# uC_board.net
KiCad netlist of a schematic drawn in EAGLE
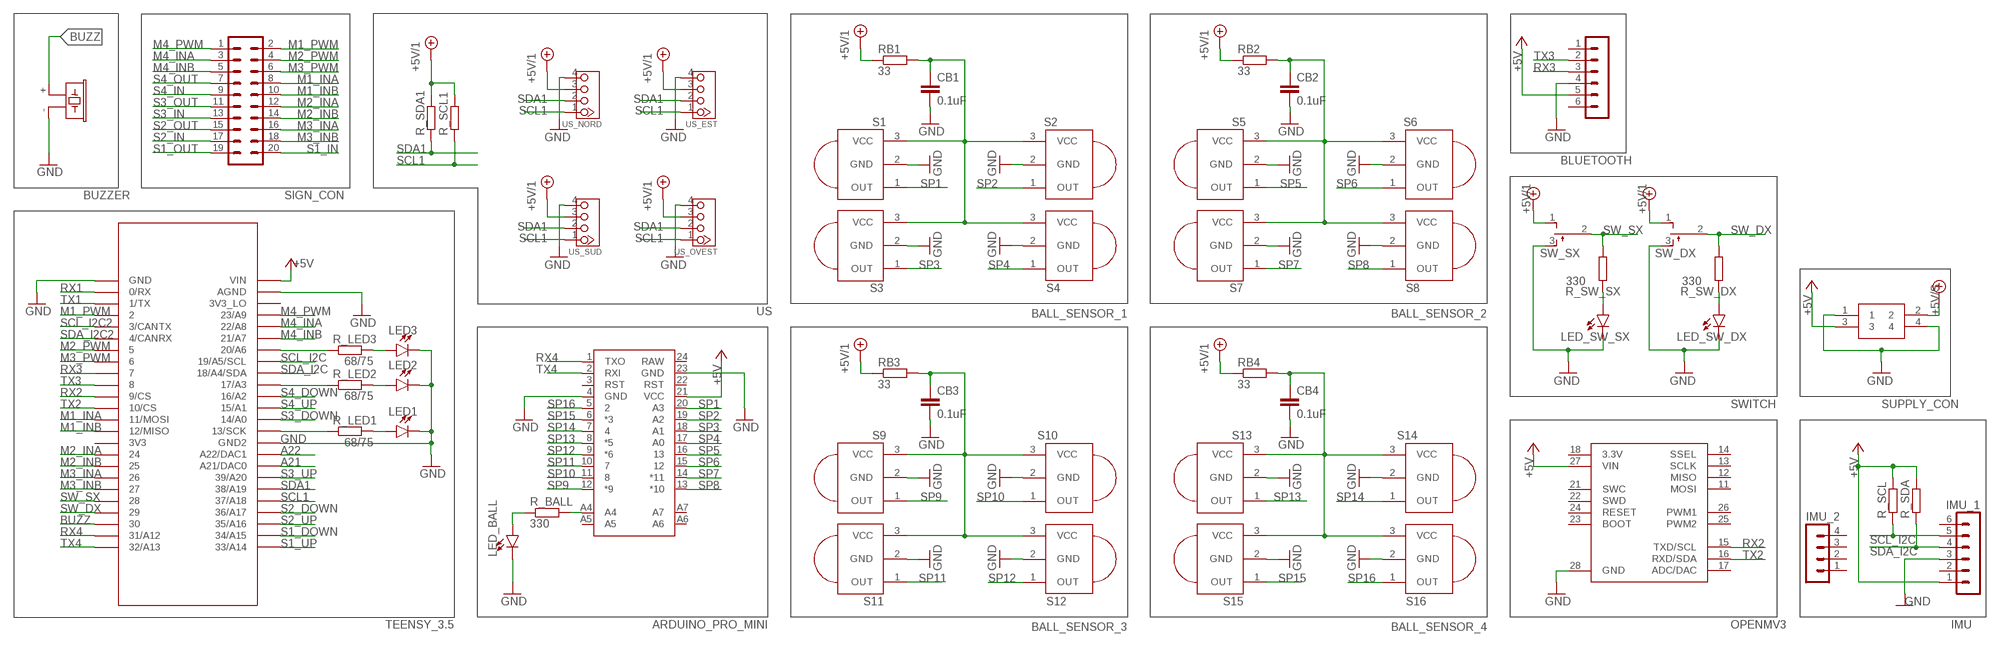
[diagram p0: schematic, sheet 1]

(export (version "E")
  (design (tool "Eeschema 10.0.6"))
  (components
    (comp (ref "ARDUINO_PRO_MINI")
      (value "ARDUINO_PRO_MINI")
      (footprint "eagle-import:ARDUINO_PRO_MINI")
      (libsource (lib "eagle-import") (part "ARDUINO_PRO_MINI"))
    )
    (comp (ref "BLUETOOTH")
      (value "MA06-1")
      (footprint "eagle-import:MA06-1")
      (libsource (lib "eagle-import") (part "MA06-1"))
    )
    (comp (ref "BUZZER")
      (value "F/CM12P")
      (footprint "eagle-import:F_CM12P")
      (libsource (lib "eagle-import") (part "F/CM12P"))
    )
    (comp (ref "CB1")
      (value "0.1uF")
      (footprint "eagle-import:C1206")
      (libsource (lib "eagle-import") (part "C-EUC1206"))
    )
    (comp (ref "CB2")
      (value "0.1uF")
      (footprint "eagle-import:C1206")
      (libsource (lib "eagle-import") (part "C-EUC1206"))
    )
    (comp (ref "CB3")
      (value "0.1uF")
      (footprint "eagle-import:C1206")
      (libsource (lib "eagle-import") (part "C-EUC1206"))
    )
    (comp (ref "CB4")
      (value "0.1uF")
      (footprint "eagle-import:C1206")
      (libsource (lib "eagle-import") (part "C-EUC1206"))
    )
    (comp (ref "IMU_1")
      (value "MA06-1")
      (footprint "eagle-import:MA06-1")
      (libsource (lib "eagle-import") (part "MA06-1"))
    )
    (comp (ref "IMU_2")
      (value "MA04-1")
      (footprint "eagle-import:MA04-1")
      (libsource (lib "eagle-import") (part "MA04-1"))
    )
    (comp (ref "J1")
      (value "39-28-1043")
      (footprint "eagle-import:39-28-1043")
      (fields (field (name "MOUSER_PART_NUMBER") "538-39-28-1043") (field (name "RS_PART_NUMBER") "4841899P"))
      (libsource (lib "eagle-import") (part "39-28-1043"))
    )
    (comp (ref "LED1")
      (value "LED3MM")
      (footprint "eagle-import:LED_3MM")
      (libsource (lib "eagle-import") (part "LED3MM"))
    )
    (comp (ref "LED2")
      (value "LED3MM")
      (footprint "eagle-import:LED_3MM")
      (libsource (lib "eagle-import") (part "LED3MM"))
    )
    (comp (ref "LED3")
      (value "LED3MM")
      (footprint "eagle-import:LED_3MM")
      (libsource (lib "eagle-import") (part "LED3MM"))
    )
    (comp (ref "LED_BALL")
      (value "LED3MM")
      (footprint "eagle-import:LED_3MM")
      (libsource (lib "eagle-import") (part "LED3MM"))
    )
    (comp (ref "LED_SW_DX")
      (value "LED3MM")
      (footprint "eagle-import:LED_3MM")
      (libsource (lib "eagle-import") (part "LED3MM"))
    )
    (comp (ref "LED_SW_SX")
      (value "LED3MM")
      (footprint "eagle-import:LED_3MM")
      (libsource (lib "eagle-import") (part "LED3MM"))
    )
    (comp (ref "RB1")
      (value "33")
      (footprint "eagle-import:R0805")
      (libsource (lib "eagle-import") (part "R-EU_R0805"))
    )
    (comp (ref "RB2")
      (value "33")
      (footprint "eagle-import:R0805")
      (libsource (lib "eagle-import") (part "R-EU_R0805"))
    )
    (comp (ref "RB3")
      (value "33")
      (footprint "eagle-import:R0805")
      (libsource (lib "eagle-import") (part "R-EU_R0805"))
    )
    (comp (ref "RB4")
      (value "33")
      (footprint "eagle-import:R0805")
      (libsource (lib "eagle-import") (part "R-EU_R0805"))
    )
    (comp (ref "R_BALL")
      (value "330")
      (footprint "eagle-import:R1206")
      (libsource (lib "eagle-import") (part "R-EU_R1206"))
    )
    (comp (ref "R_LED1")
      (value "68/75")
      (footprint "eagle-import:R0805")
      (libsource (lib "eagle-import") (part "R-EU_R0805"))
    )
    (comp (ref "R_LED2")
      (value "68/75")
      (footprint "eagle-import:R0805")
      (libsource (lib "eagle-import") (part "R-EU_R0805"))
    )
    (comp (ref "R_LED3")
      (value "68/75")
      (footprint "eagle-import:R0805")
      (libsource (lib "eagle-import") (part "R-EU_R0805"))
    )
    (comp (ref "R_SCL")
      (value "3.3k")
      (footprint "eagle-import:R0805")
      (libsource (lib "eagle-import") (part "R-EU_R0805"))
    )
    (comp (ref "R_SCL1")
      (value "3.3k")
      (footprint "eagle-import:R0805")
      (libsource (lib "eagle-import") (part "R-EU_R0805"))
    )
    (comp (ref "R_SDA")
      (value "3.3k")
      (footprint "eagle-import:R0805")
      (libsource (lib "eagle-import") (part "R-EU_R0805"))
    )
    (comp (ref "R_SDA1")
      (value "3.3k")
      (footprint "eagle-import:R0805")
      (libsource (lib "eagle-import") (part "R-EU_R0805"))
    )
    (comp (ref "R_SW_DX")
      (value "330")
      (footprint "eagle-import:R1206")
      (libsource (lib "eagle-import") (part "R-EU_R1206"))
    )
    (comp (ref "R_SW_SX")
      (value "330")
      (footprint "eagle-import:R1206")
      (libsource (lib "eagle-import") (part "R-EU_R1206"))
    )
    (comp (ref "S1")
      (value "PNA460XM")
      (footprint "eagle-import:PNA460XM")
      (libsource (lib "eagle-import") (part "PNA460XM"))
    )
    (comp (ref "S2")
      (value "PNA460XM")
      (footprint "eagle-import:PNA460XM")
      (libsource (lib "eagle-import") (part "PNA460XM"))
    )
    (comp (ref "S3")
      (value "PNA460XM")
      (footprint "eagle-import:PNA460XM")
      (libsource (lib "eagle-import") (part "PNA460XM"))
    )
    (comp (ref "S4")
      (value "PNA460XM")
      (footprint "eagle-import:PNA460XM")
      (libsource (lib "eagle-import") (part "PNA460XM"))
    )
    (comp (ref "S5")
      (value "PNA460XM")
      (footprint "eagle-import:PNA460XM")
      (libsource (lib "eagle-import") (part "PNA460XM"))
    )
    (comp (ref "S6")
      (value "PNA460XM")
      (footprint "eagle-import:PNA460XM")
      (libsource (lib "eagle-import") (part "PNA460XM"))
    )
    (comp (ref "S7")
      (value "PNA460XM")
      (footprint "eagle-import:PNA460XM")
      (libsource (lib "eagle-import") (part "PNA460XM"))
    )
    (comp (ref "S8")
      (value "PNA460XM")
      (footprint "eagle-import:PNA460XM")
      (libsource (lib "eagle-import") (part "PNA460XM"))
    )
    (comp (ref "S9")
      (value "PNA460XM")
      (footprint "eagle-import:PNA460XM")
      (libsource (lib "eagle-import") (part "PNA460XM"))
    )
    (comp (ref "S10")
      (value "PNA460XM")
      (footprint "eagle-import:PNA460XM")
      (libsource (lib "eagle-import") (part "PNA460XM"))
    )
    (comp (ref "S11")
      (value "PNA460XM")
      (footprint "eagle-import:PNA460XM")
      (libsource (lib "eagle-import") (part "PNA460XM"))
    )
    (comp (ref "S12")
      (value "PNA460XM")
      (footprint "eagle-import:PNA460XM")
      (libsource (lib "eagle-import") (part "PNA460XM"))
    )
    (comp (ref "S13")
      (value "PNA460XM")
      (footprint "eagle-import:PNA460XM")
      (libsource (lib "eagle-import") (part "PNA460XM"))
    )
    (comp (ref "S14")
      (value "PNA460XM")
      (footprint "eagle-import:PNA460XM")
      (libsource (lib "eagle-import") (part "PNA460XM"))
    )
    (comp (ref "S15")
      (value "PNA460XM")
      (footprint "eagle-import:PNA460XM")
      (libsource (lib "eagle-import") (part "PNA460XM"))
    )
    (comp (ref "S16")
      (value "PNA460XM")
      (footprint "eagle-import:PNA460XM")
      (libsource (lib "eagle-import") (part "PNA460XM"))
    )
    (comp (ref "SIGN_CON")
      (value "20V")
      (footprint "eagle-import:20V")
      (libsource (lib "eagle-import") (part "20V"))
    )
    (comp (ref "SW_DX")
      (value "TL38PO")
      (footprint "eagle-import:TL3XPO")
      (libsource (lib "eagle-import") (part "TL38PO"))
    )
    (comp (ref "SW_SX")
      (value "TL38PO")
      (footprint "eagle-import:TL3XPO")
      (libsource (lib "eagle-import") (part "TL38PO"))
    )
    (comp (ref "TEENSY_3.5")
      (value "TEENSY_3.5/3.6")
      (footprint "eagle-import:TEENSY_3.5_3.6")
      (libsource (lib "eagle-import") (part "TEENSY_3.5/3.6"))
    )
    (comp (ref "U$2")
      (value "OPENMV3")
      (footprint "eagle-import:OPENMV3")
      (libsource (lib "eagle-import") (part "OPENMV3"))
    )
    (comp (ref "US_EST")
      (value "TWIG_2.0")
      (footprint "eagle-import:2.0_1X4")
      (libsource (lib "eagle-import") (part "TWIG_2.0"))
    )
    (comp (ref "US_NORD")
      (value "TWIG_2.0")
      (footprint "eagle-import:2.0_1X4")
      (libsource (lib "eagle-import") (part "TWIG_2.0"))
    )
    (comp (ref "US_OVEST")
      (value "TWIG_2.0")
      (footprint "eagle-import:2.0_1X4")
      (libsource (lib "eagle-import") (part "TWIG_2.0"))
    )
    (comp (ref "US_SUD")
      (value "TWIG_2.0")
      (footprint "eagle-import:2.0_1X4")
      (libsource (lib "eagle-import") (part "TWIG_2.0"))
    )
  )
  (nets
    (net (code "1") (name "+5V") (class "Default")
      (node (ref "ARDUINO_PRO_MINI") (pin "21") (pinfunction "VCC_21") (pintype "power_in"))
      (node (ref "BLUETOOTH") (pin "5") (pinfunction "5_5") (pintype "passive"))
      (node (ref "IMU_1") (pin "1") (pinfunction "1_1") (pintype "passive"))
      (node (ref "J1") (pin "3") (pinfunction "3_3") (pintype "bidirectional"))
      (node (ref "R_SCL") (pin "2") (pinfunction "2_2") (pintype "passive"))
      (node (ref "R_SDA") (pin "2") (pinfunction "2_2") (pintype "passive"))
      (node (ref "TEENSY_3.5") (pin "VIN") (pinfunction "VIN_VIN") (pintype "bidirectional"))
      (node (ref "U$2") (pin "27") (pinfunction "VIN_27") (pintype "power_in"))
    )
    (net (code "2") (name "+5V{slash}1") (class "Default")
      (node (ref "J1") (pin "2") (pinfunction "2_2") (pintype "bidirectional"))
      (node (ref "RB1") (pin "1") (pinfunction "1_1") (pintype "passive"))
      (node (ref "RB2") (pin "1") (pinfunction "1_1") (pintype "passive"))
      (node (ref "RB3") (pin "1") (pinfunction "1_1") (pintype "passive"))
      (node (ref "RB4") (pin "1") (pinfunction "1_1") (pintype "passive"))
      (node (ref "R_SCL1") (pin "2") (pinfunction "2_2") (pintype "passive"))
      (node (ref "R_SDA1") (pin "2") (pinfunction "2_2") (pintype "passive"))
      (node (ref "SW_DX") (pin "1") (pinfunction "O_1") (pintype "passive"))
      (node (ref "SW_SX") (pin "1") (pinfunction "O_1") (pintype "passive"))
      (node (ref "US_EST") (pin "3") (pinfunction "3_3") (pintype "bidirectional"))
      (node (ref "US_NORD") (pin "3") (pinfunction "3_3") (pintype "bidirectional"))
      (node (ref "US_OVEST") (pin "3") (pinfunction "3_3") (pintype "bidirectional"))
      (node (ref "US_SUD") (pin "3") (pinfunction "3_3") (pintype "bidirectional"))
    )
    (net (code "3") (name "/3.3V") (class "Default")
      (node (ref "U$2") (pin "18") (pinfunction "3.3V_18") (pintype "power_in"))
    )
    (net (code "4") (name "/A21") (class "Default")
      (node (ref "TEENSY_3.5") (pin "21/DAC0") (pinfunction "A21/DAC0_21/DAC0") (pintype "bidirectional"))
    )
    (net (code "5") (name "/A22") (class "Default")
      (node (ref "TEENSY_3.5") (pin "A22/DAC1") (pinfunction "A22/DAC1_A22/DAC1") (pintype "bidirectional"))
    )
    (net (code "6") (name "/M1_INA") (class "Default")
      (node (ref "SIGN_CON") (pin "8") (pinfunction "8_8") (pintype "passive"))
      (node (ref "TEENSY_3.5") (pin "11/MOSI") (pinfunction "11/MOSI_11/MOSI") (pintype "bidirectional"))
    )
    (net (code "7") (name "/M1_INB") (class "Default")
      (node (ref "SIGN_CON") (pin "10") (pinfunction "10_10") (pintype "passive"))
      (node (ref "TEENSY_3.5") (pin "12/MISO") (pinfunction "12/MISO_12/MISO") (pintype "bidirectional"))
    )
    (net (code "8") (name "/M1_PWM") (class "Default")
      (node (ref "SIGN_CON") (pin "2") (pinfunction "2_2") (pintype "passive"))
      (node (ref "TEENSY_3.5") (pin "2") (pinfunction "2_2") (pintype "bidirectional"))
    )
    (net (code "9") (name "/M2_INA") (class "Default")
      (node (ref "SIGN_CON") (pin "12") (pinfunction "12_12") (pintype "passive"))
      (node (ref "TEENSY_3.5") (pin "24") (pinfunction "24_24") (pintype "bidirectional"))
    )
    (net (code "10") (name "/M2_INB") (class "Default")
      (node (ref "SIGN_CON") (pin "14") (pinfunction "14_14") (pintype "passive"))
      (node (ref "TEENSY_3.5") (pin "25") (pinfunction "25_25") (pintype "bidirectional"))
    )
    (net (code "11") (name "/M2_PWM") (class "Default")
      (node (ref "SIGN_CON") (pin "4") (pinfunction "4_4") (pintype "passive"))
      (node (ref "TEENSY_3.5") (pin "5") (pinfunction "5_5") (pintype "bidirectional"))
    )
    (net (code "12") (name "/M3_INA") (class "Default")
      (node (ref "SIGN_CON") (pin "16") (pinfunction "16_16") (pintype "passive"))
      (node (ref "TEENSY_3.5") (pin "26") (pinfunction "26_26") (pintype "bidirectional"))
    )
    (net (code "13") (name "/M3_INB") (class "Default")
      (node (ref "SIGN_CON") (pin "18") (pinfunction "18_18") (pintype "passive"))
      (node (ref "TEENSY_3.5") (pin "27") (pinfunction "27_27") (pintype "bidirectional"))
    )
    (net (code "14") (name "/M3_PWM") (class "Default")
      (node (ref "SIGN_CON") (pin "6") (pinfunction "6_6") (pintype "passive"))
      (node (ref "TEENSY_3.5") (pin "6") (pinfunction "6_6") (pintype "bidirectional"))
    )
    (net (code "15") (name "/M4_INA") (class "Default")
      (node (ref "SIGN_CON") (pin "3") (pinfunction "3_3") (pintype "passive"))
      (node (ref "TEENSY_3.5") (pin "22/A8") (pinfunction "22/A8_22/A8") (pintype "bidirectional"))
    )
    (net (code "16") (name "/M4_INB") (class "Default")
      (node (ref "SIGN_CON") (pin "5") (pinfunction "5_5") (pintype "passive"))
      (node (ref "TEENSY_3.5") (pin "21/A7") (pinfunction "21/A7_21/A7") (pintype "bidirectional"))
    )
    (net (code "17") (name "/M4_PWM") (class "Default")
      (node (ref "SIGN_CON") (pin "1") (pinfunction "1_1") (pintype "passive"))
      (node (ref "TEENSY_3.5") (pin "23/A9") (pinfunction "23/A9_23/A9") (pintype "bidirectional"))
    )
    (net (code "18") (name "/RAW") (class "Default")
      (node (ref "ARDUINO_PRO_MINI") (pin "24") (pinfunction "RAW_24") (pintype "power_in"))
    )
    (net (code "19") (name "/RX1") (class "Default")
      (node (ref "TEENSY_3.5") (pin "0/RX") (pinfunction "0/RX_0/RX") (pintype "bidirectional"))
    )
    (net (code "20") (name "/RX2") (class "Default")
      (node (ref "TEENSY_3.5") (pin "9/CS") (pinfunction "9/CS_9/CS") (pintype "bidirectional"))
      (node (ref "U$2") (pin "15") (pinfunction "TXD/SCL_15") (pintype "bidirectional"))
    )
    (net (code "21") (name "/RX3") (class "Default")
      (node (ref "BLUETOOTH") (pin "3") (pinfunction "3_3") (pintype "passive"))
      (node (ref "TEENSY_3.5") (pin "7") (pinfunction "7_7") (pintype "bidirectional"))
    )
    (net (code "22") (name "/RX4") (class "Default")
      (node (ref "ARDUINO_PRO_MINI") (pin "1") (pinfunction "TXO_1") (pintype "bidirectional"))
      (node (ref "TEENSY_3.5") (pin "31/A12") (pinfunction "31/A12_31/A12") (pintype "bidirectional"))
    )
    (net (code "23") (name "/S1_DOWN") (class "Default")
      (node (ref "TEENSY_3.5") (pin "34/A15") (pinfunction "34/A15_34/A15") (pintype "bidirectional"))
    )
    (net (code "24") (name "/S1_IN") (class "Default")
      (node (ref "SIGN_CON") (pin "20") (pinfunction "20_20") (pintype "passive"))
    )
    (net (code "25") (name "/S1_OUT") (class "Default")
      (node (ref "SIGN_CON") (pin "19") (pinfunction "19_19") (pintype "passive"))
    )
    (net (code "26") (name "/S1_UP") (class "Default")
      (node (ref "TEENSY_3.5") (pin "33/A14") (pinfunction "33/A14_33/A14") (pintype "bidirectional"))
    )
    (net (code "27") (name "/S2_DOWN") (class "Default")
      (node (ref "TEENSY_3.5") (pin "36/A17") (pinfunction "36/A17_36/A17") (pintype "bidirectional"))
    )
    (net (code "28") (name "/S2_IN") (class "Default")
      (node (ref "SIGN_CON") (pin "17") (pinfunction "17_17") (pintype "passive"))
    )
    (net (code "29") (name "/S2_OUT") (class "Default")
      (node (ref "SIGN_CON") (pin "15") (pinfunction "15_15") (pintype "passive"))
    )
    (net (code "30") (name "/S2_UP") (class "Default")
      (node (ref "TEENSY_3.5") (pin "35/A16") (pinfunction "35/A16_35/A16") (pintype "bidirectional"))
    )
    (net (code "31") (name "/S3_DOWN") (class "Default")
      (node (ref "TEENSY_3.5") (pin "14/A0") (pinfunction "14/A0_14/A0") (pintype "bidirectional"))
    )
    (net (code "32") (name "/S3_IN") (class "Default")
      (node (ref "SIGN_CON") (pin "13") (pinfunction "13_13") (pintype "passive"))
    )
    (net (code "33") (name "/S3_OUT") (class "Default")
      (node (ref "SIGN_CON") (pin "11") (pinfunction "11_11") (pintype "passive"))
    )
    (net (code "34") (name "/S3_UP") (class "Default")
      (node (ref "TEENSY_3.5") (pin "39/A20") (pinfunction "39/A20_39/A20") (pintype "bidirectional"))
    )
    (net (code "35") (name "/S4_DOWN") (class "Default")
      (node (ref "TEENSY_3.5") (pin "16/A2") (pinfunction "16/A2_16/A2") (pintype "bidirectional"))
    )
    (net (code "36") (name "/S4_IN") (class "Default")
      (node (ref "SIGN_CON") (pin "9") (pinfunction "9_9") (pintype "passive"))
    )
    (net (code "37") (name "/S4_OUT") (class "Default")
      (node (ref "SIGN_CON") (pin "7") (pinfunction "7_7") (pintype "passive"))
    )
    (net (code "38") (name "/S4_UP") (class "Default")
      (node (ref "TEENSY_3.5") (pin "15/A1") (pinfunction "15/A1_15/A1") (pintype "bidirectional"))
    )
    (net (code "39") (name "/SCL1") (class "Default")
      (node (ref "R_SCL1") (pin "1") (pinfunction "1_1") (pintype "passive"))
      (node (ref "TEENSY_3.5") (pin "37/A18") (pinfunction "37/A18_37/A18") (pintype "bidirectional"))
      (node (ref "US_EST") (pin "1") (pinfunction "1_1") (pintype "bidirectional"))
      (node (ref "US_NORD") (pin "1") (pinfunction "1_1") (pintype "bidirectional"))
      (node (ref "US_OVEST") (pin "1") (pinfunction "1_1") (pintype "bidirectional"))
      (node (ref "US_SUD") (pin "1") (pinfunction "1_1") (pintype "bidirectional"))
    )
    (net (code "40") (name "/SCL_I2C") (class "Default")
      (node (ref "IMU_1") (pin "5") (pinfunction "5_5") (pintype "passive"))
      (node (ref "R_SCL") (pin "1") (pinfunction "1_1") (pintype "passive"))
      (node (ref "TEENSY_3.5") (pin "19/A5/SCL") (pinfunction "19/A5/SCL_19/A5/SCL") (pintype "bidirectional"))
    )
    (net (code "41") (name "/SCL_I2C2") (class "Default")
      (node (ref "TEENSY_3.5") (pin "3/CANTX") (pinfunction "3/CANTX_3/CANTX") (pintype "bidirectional"))
    )
    (net (code "42") (name "/SDA1") (class "Default")
      (node (ref "R_SDA1") (pin "1") (pinfunction "1_1") (pintype "passive"))
      (node (ref "TEENSY_3.5") (pin "38/A19") (pinfunction "38/A19_38/A19") (pintype "bidirectional"))
      (node (ref "US_EST") (pin "2") (pinfunction "2_2") (pintype "bidirectional"))
      (node (ref "US_NORD") (pin "2") (pinfunction "2_2") (pintype "bidirectional"))
      (node (ref "US_OVEST") (pin "2") (pinfunction "2_2") (pintype "bidirectional"))
      (node (ref "US_SUD") (pin "2") (pinfunction "2_2") (pintype "bidirectional"))
    )
    (net (code "43") (name "/SDA_I2C") (class "Default")
      (node (ref "IMU_1") (pin "4") (pinfunction "4_4") (pintype "passive"))
      (node (ref "R_SDA") (pin "1") (pinfunction "1_1") (pintype "passive"))
      (node (ref "TEENSY_3.5") (pin "18/A4/SDA") (pinfunction "18/A4/SDA_18/A4/SDA") (pintype "bidirectional"))
    )
    (net (code "44") (name "/SDA_I2C2") (class "Default")
      (node (ref "TEENSY_3.5") (pin "4/CANRX") (pinfunction "4/CANRX_4/CANRX") (pintype "bidirectional"))
    )
    (net (code "45") (name "/SP1") (class "Default")
      (node (ref "ARDUINO_PRO_MINI") (pin "20") (pinfunction "A3_20") (pintype "bidirectional"))
      (node (ref "S1") (pin "1") (pinfunction "OUT_1") (pintype "output"))
    )
    (net (code "46") (name "/SP2") (class "Default")
      (node (ref "ARDUINO_PRO_MINI") (pin "19") (pinfunction "A2_19") (pintype "bidirectional"))
      (node (ref "S2") (pin "1") (pinfunction "OUT_1") (pintype "output"))
    )
    (net (code "47") (name "/SP3") (class "Default")
      (node (ref "ARDUINO_PRO_MINI") (pin "18") (pinfunction "A1_18") (pintype "bidirectional"))
      (node (ref "S3") (pin "1") (pinfunction "OUT_1") (pintype "output"))
    )
    (net (code "48") (name "/SP4") (class "Default")
      (node (ref "ARDUINO_PRO_MINI") (pin "17") (pinfunction "A0_17") (pintype "bidirectional"))
      (node (ref "S4") (pin "1") (pinfunction "OUT_1") (pintype "output"))
    )
    (net (code "49") (name "/SP5") (class "Default")
      (node (ref "ARDUINO_PRO_MINI") (pin "16") (pinfunction "13_16") (pintype "bidirectional"))
      (node (ref "S5") (pin "1") (pinfunction "OUT_1") (pintype "output"))
    )
    (net (code "50") (name "/SP6") (class "Default")
      (node (ref "ARDUINO_PRO_MINI") (pin "15") (pinfunction "12_15") (pintype "bidirectional"))
      (node (ref "S6") (pin "1") (pinfunction "OUT_1") (pintype "output"))
    )
    (net (code "51") (name "/SP7") (class "Default")
      (node (ref "ARDUINO_PRO_MINI") (pin "14") (pinfunction "*11_14") (pintype "bidirectional"))
      (node (ref "S7") (pin "1") (pinfunction "OUT_1") (pintype "output"))
    )
    (net (code "52") (name "/SP8") (class "Default")
      (node (ref "ARDUINO_PRO_MINI") (pin "13") (pinfunction "*10_13") (pintype "bidirectional"))
      (node (ref "S8") (pin "1") (pinfunction "OUT_1") (pintype "output"))
    )
    (net (code "53") (name "/SP9") (class "Default")
      (node (ref "ARDUINO_PRO_MINI") (pin "12") (pinfunction "*9_12") (pintype "bidirectional"))
      (node (ref "S9") (pin "1") (pinfunction "OUT_1") (pintype "output"))
    )
    (net (code "54") (name "/SP10") (class "Default")
      (node (ref "ARDUINO_PRO_MINI") (pin "11") (pinfunction "8_11") (pintype "bidirectional"))
      (node (ref "S10") (pin "1") (pinfunction "OUT_1") (pintype "output"))
    )
    (net (code "55") (name "/SP11") (class "Default")
      (node (ref "ARDUINO_PRO_MINI") (pin "10") (pinfunction "7_10") (pintype "bidirectional"))
      (node (ref "S11") (pin "1") (pinfunction "OUT_1") (pintype "output"))
    )
    (net (code "56") (name "/SP12") (class "Default")
      (node (ref "ARDUINO_PRO_MINI") (pin "9") (pinfunction "*6_9") (pintype "bidirectional"))
      (node (ref "S12") (pin "1") (pinfunction "OUT_1") (pintype "output"))
    )
    (net (code "57") (name "/SP13") (class "Default")
      (node (ref "ARDUINO_PRO_MINI") (pin "8") (pinfunction "*5_8") (pintype "bidirectional"))
      (node (ref "S13") (pin "1") (pinfunction "OUT_1") (pintype "output"))
    )
    (net (code "58") (name "/SP14") (class "Default")
      (node (ref "ARDUINO_PRO_MINI") (pin "7") (pinfunction "4_7") (pintype "bidirectional"))
      (node (ref "S14") (pin "1") (pinfunction "OUT_1") (pintype "output"))
    )
    (net (code "59") (name "/SP15") (class "Default")
      (node (ref "ARDUINO_PRO_MINI") (pin "6") (pinfunction "*3_6") (pintype "bidirectional"))
      (node (ref "S15") (pin "1") (pinfunction "OUT_1") (pintype "output"))
    )
    (net (code "60") (name "/SP16") (class "Default")
      (node (ref "ARDUINO_PRO_MINI") (pin "5") (pinfunction "2_5") (pintype "bidirectional"))
      (node (ref "S16") (pin "1") (pinfunction "OUT_1") (pintype "output"))
    )
    (net (code "61") (name "/SW_DX") (class "Default")
      (node (ref "R_SW_DX") (pin "2") (pinfunction "2_2") (pintype "passive"))
      (node (ref "SW_DX") (pin "2") (pinfunction "P_2") (pintype "passive"))
      (node (ref "TEENSY_3.5") (pin "29") (pinfunction "29_29") (pintype "bidirectional"))
    )
    (net (code "62") (name "/SW_SX") (class "Default")
      (node (ref "R_SW_SX") (pin "2") (pinfunction "2_2") (pintype "passive"))
      (node (ref "SW_SX") (pin "2") (pinfunction "P_2") (pintype "passive"))
      (node (ref "TEENSY_3.5") (pin "28") (pinfunction "28_28") (pintype "bidirectional"))
    )
    (net (code "63") (name "/TX1") (class "Default")
      (node (ref "TEENSY_3.5") (pin "1/TX") (pinfunction "1/TX_1/TX") (pintype "bidirectional"))
    )
    (net (code "64") (name "/TX2") (class "Default")
      (node (ref "TEENSY_3.5") (pin "10/CS") (pinfunction "10/CS_10/CS") (pintype "bidirectional"))
      (node (ref "U$2") (pin "16") (pinfunction "RXD/SDA_16") (pintype "bidirectional"))
    )
    (net (code "65") (name "/TX3") (class "Default")
      (node (ref "BLUETOOTH") (pin "2") (pinfunction "2_2") (pintype "passive"))
      (node (ref "TEENSY_3.5") (pin "8") (pinfunction "8_8") (pintype "bidirectional"))
    )
    (net (code "66") (name "/TX4") (class "Default")
      (node (ref "ARDUINO_PRO_MINI") (pin "2") (pinfunction "RXI_2") (pintype "bidirectional"))
      (node (ref "TEENSY_3.5") (pin "32/A13") (pinfunction "32/A13_32/A13") (pintype "bidirectional"))
    )
    (net (code "67") (name "BUZZ") (class "Default")
      (node (ref "BUZZER") (pin "+") (pinfunction "1_+") (pintype "passive"))
      (node (ref "TEENSY_3.5") (pin "30") (pinfunction "30_30") (pintype "bidirectional"))
    )
    (net (code "68") (name "GND") (class "Default")
      (node (ref "ARDUINO_PRO_MINI") (pin "23") (pinfunction "GND_23") (pintype "power_in"))
      (node (ref "ARDUINO_PRO_MINI") (pin "4") (pinfunction "GND_4") (pintype "power_in"))
      (node (ref "BLUETOOTH") (pin "4") (pinfunction "4_4") (pintype "passive"))
      (node (ref "BUZZER") (pin "-") (pinfunction "2_-") (pintype "passive"))
      (node (ref "CB1") (pin "2") (pinfunction "2_2") (pintype "passive"))
      (node (ref "CB2") (pin "2") (pinfunction "2_2") (pintype "passive"))
      (node (ref "CB3") (pin "2") (pinfunction "2_2") (pintype "passive"))
      (node (ref "CB4") (pin "2") (pinfunction "2_2") (pintype "passive"))
      (node (ref "IMU_1") (pin "3") (pinfunction "3_3") (pintype "passive"))
      (node (ref "J1") (pin "1") (pinfunction "1_1") (pintype "bidirectional"))
      (node (ref "J1") (pin "4") (pinfunction "4_4") (pintype "bidirectional"))
      (node (ref "LED1") (pin "K") (pinfunction "C_K") (pintype "passive"))
      (node (ref "LED2") (pin "K") (pinfunction "C_K") (pintype "passive"))
      (node (ref "LED3") (pin "K") (pinfunction "C_K") (pintype "passive"))
      (node (ref "LED_BALL") (pin "K") (pinfunction "C_K") (pintype "passive"))
      (node (ref "LED_SW_DX") (pin "K") (pinfunction "C_K") (pintype "passive"))
      (node (ref "LED_SW_SX") (pin "K") (pinfunction "C_K") (pintype "passive"))
      (node (ref "S1") (pin "2") (pinfunction "GND_2") (pintype "power_in"))
      (node (ref "S10") (pin "2") (pinfunction "GND_2") (pintype "power_in"))
      (node (ref "S11") (pin "2") (pinfunction "GND_2") (pintype "power_in"))
      (node (ref "S12") (pin "2") (pinfunction "GND_2") (pintype "power_in"))
      (node (ref "S13") (pin "2") (pinfunction "GND_2") (pintype "power_in"))
      (node (ref "S14") (pin "2") (pinfunction "GND_2") (pintype "power_in"))
      (node (ref "S15") (pin "2") (pinfunction "GND_2") (pintype "power_in"))
      (node (ref "S16") (pin "2") (pinfunction "GND_2") (pintype "power_in"))
      (node (ref "S2") (pin "2") (pinfunction "GND_2") (pintype "power_in"))
      (node (ref "S3") (pin "2") (pinfunction "GND_2") (pintype "power_in"))
      (node (ref "S4") (pin "2") (pinfunction "GND_2") (pintype "power_in"))
      (node (ref "S5") (pin "2") (pinfunction "GND_2") (pintype "power_in"))
      (node (ref "S6") (pin "2") (pinfunction "GND_2") (pintype "power_in"))
      (node (ref "S7") (pin "2") (pinfunction "GND_2") (pintype "power_in"))
      (node (ref "S8") (pin "2") (pinfunction "GND_2") (pintype "power_in"))
      (node (ref "S9") (pin "2") (pinfunction "GND_2") (pintype "power_in"))
      (node (ref "SW_DX") (pin "3") (pinfunction "S_3") (pintype "passive"))
      (node (ref "SW_SX") (pin "3") (pinfunction "S_3") (pintype "passive"))
      (node (ref "TEENSY_3.5") (pin "AGND") (pinfunction "AGND_AGND") (pintype "bidirectional"))
      (node (ref "TEENSY_3.5") (pin "GND") (pinfunction "GND_GND") (pintype "bidirectional"))
      (node (ref "TEENSY_3.5") (pin "GND2") (pinfunction "GND2_GND2") (pintype "bidirectional"))
      (node (ref "U$2") (pin "28") (pinfunction "GND_28") (pintype "power_in"))
      (node (ref "US_EST") (pin "4") (pinfunction "4_4") (pintype "bidirectional"))
      (node (ref "US_NORD") (pin "4") (pinfunction "4_4") (pintype "bidirectional"))
      (node (ref "US_OVEST") (pin "4") (pinfunction "4_4") (pintype "bidirectional"))
      (node (ref "US_SUD") (pin "4") (pinfunction "4_4") (pintype "bidirectional"))
    )
    (net (code "69") (name "Net-(ARDUINO_PRO_MINI-PadA4)") (class "Default")
      (node (ref "ARDUINO_PRO_MINI") (pin "A4") (pinfunction "A4_A4") (pintype "bidirectional"))
      (node (ref "R_BALL") (pin "2") (pinfunction "2_2") (pintype "passive"))
    )
    (net (code "70") (name "Net-(LED1-PadA)") (class "Default")
      (node (ref "LED1") (pin "A") (pinfunction "A_A") (pintype "passive"))
      (node (ref "R_LED1") (pin "2") (pinfunction "2_2") (pintype "passive"))
    )
    (net (code "71") (name "Net-(LED2-PadA)") (class "Default")
      (node (ref "LED2") (pin "A") (pinfunction "A_A") (pintype "passive"))
      (node (ref "R_LED2") (pin "2") (pinfunction "2_2") (pintype "passive"))
    )
    (net (code "72") (name "Net-(LED3-PadA)") (class "Default")
      (node (ref "LED3") (pin "A") (pinfunction "A_A") (pintype "passive"))
      (node (ref "R_LED3") (pin "2") (pinfunction "2_2") (pintype "passive"))
    )
    (net (code "73") (name "Net-(LED_BALL-PadA)") (class "Default")
      (node (ref "LED_BALL") (pin "A") (pinfunction "A_A") (pintype "passive"))
      (node (ref "R_BALL") (pin "1") (pinfunction "1_1") (pintype "passive"))
    )
    (net (code "74") (name "Net-(LED_SW_DX-PadA)") (class "Default")
      (node (ref "LED_SW_DX") (pin "A") (pinfunction "A_A") (pintype "passive"))
      (node (ref "R_SW_DX") (pin "1") (pinfunction "1_1") (pintype "passive"))
    )
    (net (code "75") (name "Net-(LED_SW_SX-PadA)") (class "Default")
      (node (ref "LED_SW_SX") (pin "A") (pinfunction "A_A") (pintype "passive"))
      (node (ref "R_SW_SX") (pin "1") (pinfunction "1_1") (pintype "passive"))
    )
    (net (code "76") (name "Net-(R_LED1-Pad1)") (class "Default")
      (node (ref "R_LED1") (pin "1") (pinfunction "1_1") (pintype "passive"))
      (node (ref "TEENSY_3.5") (pin "13/SCK") (pinfunction "13/SCK_13/SCK") (pintype "bidirectional"))
    )
    (net (code "77") (name "Net-(R_LED2-Pad1)") (class "Default")
      (node (ref "R_LED2") (pin "1") (pinfunction "1_1") (pintype "passive"))
      (node (ref "TEENSY_3.5") (pin "17/A3") (pinfunction "17/A3_17/A3") (pintype "bidirectional"))
    )
    (net (code "78") (name "Net-(R_LED3-Pad1)") (class "Default")
      (node (ref "R_LED3") (pin "1") (pinfunction "1_1") (pintype "passive"))
      (node (ref "TEENSY_3.5") (pin "20/A6") (pinfunction "20/A6_20/A6") (pintype "bidirectional"))
    )
    (net (code "79") (name "Net-(S1-VCC)") (class "Default")
      (node (ref "CB1") (pin "1") (pinfunction "1_1") (pintype "passive"))
      (node (ref "RB1") (pin "2") (pinfunction "2_2") (pintype "passive"))
      (node (ref "S1") (pin "3") (pinfunction "VCC_3") (pintype "power_in"))
      (node (ref "S2") (pin "3") (pinfunction "VCC_3") (pintype "power_in"))
      (node (ref "S3") (pin "3") (pinfunction "VCC_3") (pintype "power_in"))
      (node (ref "S4") (pin "3") (pinfunction "VCC_3") (pintype "power_in"))
    )
    (net (code "80") (name "Net-(S5-VCC)") (class "Default")
      (node (ref "CB2") (pin "1") (pinfunction "1_1") (pintype "passive"))
      (node (ref "RB2") (pin "2") (pinfunction "2_2") (pintype "passive"))
      (node (ref "S5") (pin "3") (pinfunction "VCC_3") (pintype "power_in"))
      (node (ref "S6") (pin "3") (pinfunction "VCC_3") (pintype "power_in"))
      (node (ref "S7") (pin "3") (pinfunction "VCC_3") (pintype "power_in"))
      (node (ref "S8") (pin "3") (pinfunction "VCC_3") (pintype "power_in"))
    )
    (net (code "81") (name "Net-(S10-VCC)") (class "Default")
      (node (ref "CB3") (pin "1") (pinfunction "1_1") (pintype "passive"))
      (node (ref "RB3") (pin "2") (pinfunction "2_2") (pintype "passive"))
      (node (ref "S10") (pin "3") (pinfunction "VCC_3") (pintype "power_in"))
      (node (ref "S11") (pin "3") (pinfunction "VCC_3") (pintype "power_in"))
      (node (ref "S12") (pin "3") (pinfunction "VCC_3") (pintype "power_in"))
      (node (ref "S9") (pin "3") (pinfunction "VCC_3") (pintype "power_in"))
    )
    (net (code "82") (name "Net-(S13-VCC)") (class "Default")
      (node (ref "CB4") (pin "1") (pinfunction "1_1") (pintype "passive"))
      (node (ref "RB4") (pin "2") (pinfunction "2_2") (pintype "passive"))
      (node (ref "S13") (pin "3") (pinfunction "VCC_3") (pintype "power_in"))
      (node (ref "S14") (pin "3") (pinfunction "VCC_3") (pintype "power_in"))
      (node (ref "S15") (pin "3") (pinfunction "VCC_3") (pintype "power_in"))
      (node (ref "S16") (pin "3") (pinfunction "VCC_3") (pintype "power_in"))
    )
    (net (code "83") (name "unconnected-(ARDUINO_PRO_MINI-PadA5)") (class "Default")
      (node (ref "ARDUINO_PRO_MINI") (pin "A5") (pinfunction "A5_A5") (pintype "bidirectional"))
    )
    (net (code "84") (name "unconnected-(ARDUINO_PRO_MINI-PadA6)") (class "Default")
      (node (ref "ARDUINO_PRO_MINI") (pin "A6") (pinfunction "A6_A6") (pintype "bidirectional"))
    )
    (net (code "85") (name "unconnected-(ARDUINO_PRO_MINI-PadA7)") (class "Default")
      (node (ref "ARDUINO_PRO_MINI") (pin "A7") (pinfunction "A7_A7") (pintype "bidirectional"))
    )
    (net (code "86") (name "unconnected-(ARDUINO_PRO_MINI-RST-Pad3)") (class "Default")
      (node (ref "ARDUINO_PRO_MINI") (pin "3") (pinfunction "RST_3") (pintype "bidirectional"))
    )
    (net (code "87") (name "unconnected-(ARDUINO_PRO_MINI-RST-Pad22)") (class "Default")
      (node (ref "ARDUINO_PRO_MINI") (pin "22") (pinfunction "RST_22") (pintype "bidirectional"))
    )
    (net (code "88") (name "unconnected-(BLUETOOTH-Pad1)") (class "Default")
      (node (ref "BLUETOOTH") (pin "1") (pinfunction "1_1") (pintype "passive"))
    )
    (net (code "89") (name "unconnected-(BLUETOOTH-Pad6)") (class "Default")
      (node (ref "BLUETOOTH") (pin "6") (pinfunction "6_6") (pintype "passive"))
    )
    (net (code "90") (name "unconnected-(IMU_1-Pad2)") (class "Default")
      (node (ref "IMU_1") (pin "2") (pinfunction "2_2") (pintype "passive"))
    )
    (net (code "91") (name "unconnected-(IMU_1-Pad6)") (class "Default")
      (node (ref "IMU_1") (pin "6") (pinfunction "6_6") (pintype "passive"))
    )
    (net (code "92") (name "unconnected-(IMU_2-Pad1)") (class "Default")
      (node (ref "IMU_2") (pin "1") (pinfunction "1_1") (pintype "passive"))
    )
    (net (code "93") (name "unconnected-(IMU_2-Pad2)") (class "Default")
      (node (ref "IMU_2") (pin "2") (pinfunction "2_2") (pintype "passive"))
    )
    (net (code "94") (name "unconnected-(IMU_2-Pad3)") (class "Default")
      (node (ref "IMU_2") (pin "3") (pinfunction "3_3") (pintype "passive"))
    )
    (net (code "95") (name "unconnected-(IMU_2-Pad4)") (class "Default")
      (node (ref "IMU_2") (pin "4") (pinfunction "4_4") (pintype "passive"))
    )
    (net (code "96") (name "unconnected-(TEENSY_3.5-Pad3V3)") (class "Default")
      (node (ref "TEENSY_3.5") (pin "3V3") (pinfunction "3V3_3V3") (pintype "bidirectional"))
    )
    (net (code "97") (name "unconnected-(TEENSY_3.5-Pad3V3_LO)") (class "Default")
      (node (ref "TEENSY_3.5") (pin "3V3_LO") (pinfunction "3V3_LO_3V3_LO") (pintype "bidirectional"))
    )
    (net (code "98") (name "unconnected-(U$2-ADC{slash}DAC-Pad17)") (class "Default")
      (node (ref "U$2") (pin "17") (pinfunction "ADC/DAC_17") (pintype "bidirectional"))
    )
    (net (code "99") (name "unconnected-(U$2-BOOT-Pad23)") (class "Default")
      (node (ref "U$2") (pin "23") (pinfunction "BOOT_23") (pintype "bidirectional"))
    )
    (net (code "100") (name "unconnected-(U$2-MISO-Pad12)") (class "Default")
      (node (ref "U$2") (pin "12") (pinfunction "MISO_12") (pintype "bidirectional"))
    )
    (net (code "101") (name "unconnected-(U$2-MOSI-Pad11)") (class "Default")
      (node (ref "U$2") (pin "11") (pinfunction "MOSI_11") (pintype "bidirectional"))
    )
    (net (code "102") (name "unconnected-(U$2-PWM1-Pad26)") (class "Default")
      (node (ref "U$2") (pin "26") (pinfunction "PWM1_26") (pintype "bidirectional"))
    )
    (net (code "103") (name "unconnected-(U$2-PWM2-Pad25)") (class "Default")
      (node (ref "U$2") (pin "25") (pinfunction "PWM2_25") (pintype "bidirectional"))
    )
    (net (code "104") (name "unconnected-(U$2-RESET-Pad24)") (class "Default")
      (node (ref "U$2") (pin "24") (pinfunction "RESET_24") (pintype "bidirectional"))
    )
    (net (code "105") (name "unconnected-(U$2-SCLK-Pad13)") (class "Default")
      (node (ref "U$2") (pin "13") (pinfunction "SCLK_13") (pintype "bidirectional"))
    )
    (net (code "106") (name "unconnected-(U$2-SSEL-Pad14)") (class "Default")
      (node (ref "U$2") (pin "14") (pinfunction "SSEL_14") (pintype "bidirectional"))
    )
    (net (code "107") (name "unconnected-(U$2-SWC-Pad21)") (class "Default")
      (node (ref "U$2") (pin "21") (pinfunction "SWC_21") (pintype "bidirectional"))
    )
    (net (code "108") (name "unconnected-(U$2-SWD-Pad22)") (class "Default")
      (node (ref "U$2") (pin "22") (pinfunction "SWD_22") (pintype "bidirectional"))
    )
  )
)
